# Totem.net
KiCad netlist of a schematic drawn in EAGLE
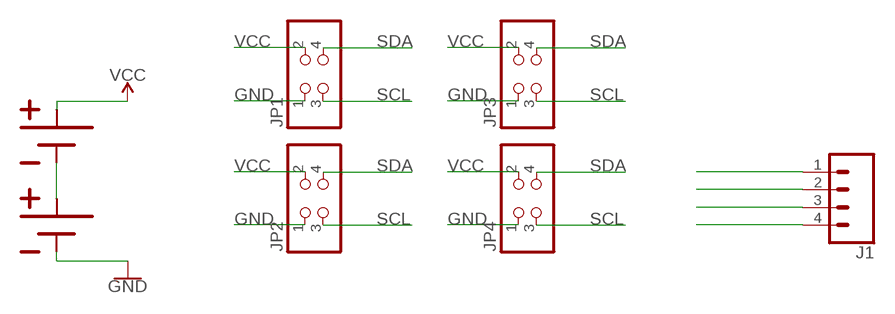
[diagram p0: schematic, sheet 1]

(export (version "E")
  (design (tool "Eeschema 10.0.6"))
  (components
    (comp (ref "J1")
      (value "CONN_04")
      (footprint "eagle-import:1X04")
      (libsource (lib "eagle-import") (part "CONN_04"))
    )
    (comp (ref "JP1")
      (value "PINHD-2X2")
      (footprint "eagle-import:2X02")
      (libsource (lib "eagle-import") (part "PINHD-2X2"))
    )
    (comp (ref "JP2")
      (value "PINHD-2X2")
      (footprint "eagle-import:2X02")
      (libsource (lib "eagle-import") (part "PINHD-2X2"))
    )
    (comp (ref "JP3")
      (value "PINHD-2X2")
      (footprint "eagle-import:2X02")
      (libsource (lib "eagle-import") (part "PINHD-2X2"))
    )
    (comp (ref "JP4")
      (value "PINHD-2X2")
      (footprint "eagle-import:2X02")
      (libsource (lib "eagle-import") (part "PINHD-2X2"))
    )
    (comp (ref "U$1")
      (value "EAGLEAABATTERY")
      (footprint "eagle-import:ONEAAHOLDER")
      (libsource (lib "eagle-import") (part "EAGLEAABATTERY"))
    )
    (comp (ref "U$2")
      (value "EAGLEAABATTERY")
      (footprint "eagle-import:ONEAAHOLDER")
      (libsource (lib "eagle-import") (part "EAGLEAABATTERY"))
    )
  )
  (nets
    (net (code "1") (name "/SCL") (class "Default")
      (node (ref "J1") (pin "3") (pinfunction "3_3") (pintype "passive"))
      (node (ref "JP1") (pin "3") (pinfunction "3_3") (pintype "passive"))
      (node (ref "JP2") (pin "3") (pinfunction "3_3") (pintype "passive"))
      (node (ref "JP3") (pin "3") (pinfunction "3_3") (pintype "passive"))
      (node (ref "JP4") (pin "3") (pinfunction "3_3") (pintype "passive"))
    )
    (net (code "2") (name "/SDA") (class "Default")
      (node (ref "J1") (pin "2") (pinfunction "2_2") (pintype "passive"))
      (node (ref "JP1") (pin "4") (pinfunction "4_4") (pintype "passive"))
      (node (ref "JP2") (pin "4") (pinfunction "4_4") (pintype "passive"))
      (node (ref "JP3") (pin "4") (pinfunction "4_4") (pintype "passive"))
      (node (ref "JP4") (pin "4") (pinfunction "4_4") (pintype "passive"))
    )
    (net (code "3") (name "GND") (class "Default")
      (node (ref "J1") (pin "4") (pinfunction "4_4") (pintype "passive"))
      (node (ref "JP1") (pin "1") (pinfunction "1_1") (pintype "passive"))
      (node (ref "JP2") (pin "1") (pinfunction "1_1") (pintype "passive"))
      (node (ref "JP3") (pin "1") (pinfunction "1_1") (pintype "passive"))
      (node (ref "JP4") (pin "1") (pinfunction "1_1") (pintype "passive"))
      (node (ref "U$2") (pin "NEG") (pinfunction "NEG_NEG") (pintype "bidirectional"))
    )
    (net (code "4") (name "Net-(U$1-PadNEG)") (class "Default")
      (node (ref "U$1") (pin "NEG") (pinfunction "NEG_NEG") (pintype "bidirectional"))
      (node (ref "U$2") (pin "POS") (pinfunction "POS_POS") (pintype "bidirectional"))
    )
    (net (code "5") (name "VCC") (class "Default")
      (node (ref "J1") (pin "1") (pinfunction "1_1") (pintype "passive"))
      (node (ref "JP1") (pin "2") (pinfunction "2_2") (pintype "passive"))
      (node (ref "JP2") (pin "2") (pinfunction "2_2") (pintype "passive"))
      (node (ref "JP3") (pin "2") (pinfunction "2_2") (pintype "passive"))
      (node (ref "JP4") (pin "2") (pinfunction "2_2") (pintype "passive"))
      (node (ref "U$1") (pin "POS") (pinfunction "POS_POS") (pintype "bidirectional"))
    )
  )
)
